# SPITEMP3.net
KiCad netlist of a schematic drawn in Altium Designer
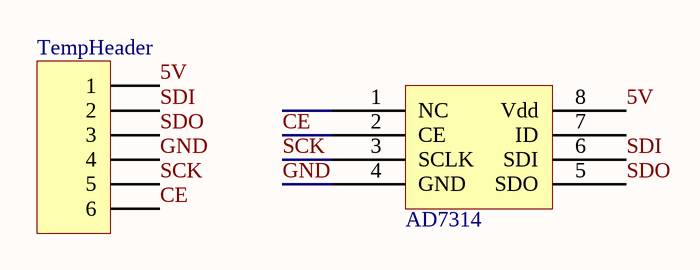
[diagram p0: SPITEMP3.SchDoc]

(export (version "E")
  (design (tool "Eeschema 10.0.6"))
  (components
    (comp (ref "AD7314")
      (value "SPI Temp Sensor")
      (footprint "AD7314")
      (description "SPI Temp Sensor (8-lead MSOP")
      (libsource (lib "AD7314") (part "AD7314"))
    )
    (comp (ref "TempHeader")
      (value "Header 6")
      (footprint "HDR1X6")
      (description "Header, 6-Pin")
      (fields (field (name "PUBLISHER") "Altium Limited"))
      (libsource (lib "Miscellaneous Connectors") (part "Header 6"))
    )
  )
  (nets
    (net (code "1") (name "/5V") (class "Default")
      (node (ref "AD7314") (pin "8") (pinfunction "Vdd_8") (pintype "passive"))
      (node (ref "TempHeader") (pin "1") (pinfunction "1_1") (pintype "passive"))
    )
    (net (code "2") (name "/CE") (class "Default")
      (node (ref "AD7314") (pin "2") (pinfunction "CE_2") (pintype "passive"))
      (node (ref "TempHeader") (pin "6") (pinfunction "6_6") (pintype "passive"))
    )
    (net (code "3") (name "/GND") (class "Default")
      (node (ref "AD7314") (pin "4") (pinfunction "GND_4") (pintype "passive"))
      (node (ref "TempHeader") (pin "4") (pinfunction "4_4") (pintype "passive"))
    )
    (net (code "4") (name "/SCK") (class "Default")
      (node (ref "AD7314") (pin "3") (pinfunction "SCLK_3") (pintype "passive"))
      (node (ref "TempHeader") (pin "5") (pinfunction "5_5") (pintype "passive"))
    )
    (net (code "5") (name "/SDI") (class "Default")
      (node (ref "AD7314") (pin "6") (pinfunction "SDI_6") (pintype "passive"))
      (node (ref "TempHeader") (pin "2") (pinfunction "2_2") (pintype "passive"))
    )
    (net (code "6") (name "/SDO") (class "Default")
      (node (ref "AD7314") (pin "5") (pinfunction "SDO_5") (pintype "passive"))
      (node (ref "TempHeader") (pin "3") (pinfunction "3_3") (pintype "passive"))
    )
    (net (code "7") (name "unconnected-(AD7314-ID-Pad7)") (class "Default")
      (node (ref "AD7314") (pin "7") (pinfunction "ID_7") (pintype "passive"))
    )
    (net (code "8") (name "unconnected-(AD7314-NC-Pad1)") (class "Default")
      (node (ref "AD7314") (pin "1") (pinfunction "NC_1") (pintype "passive"))
    )
  )
)
